# Blinky_v2.net
KiCad netlist of a schematic drawn in EAGLE
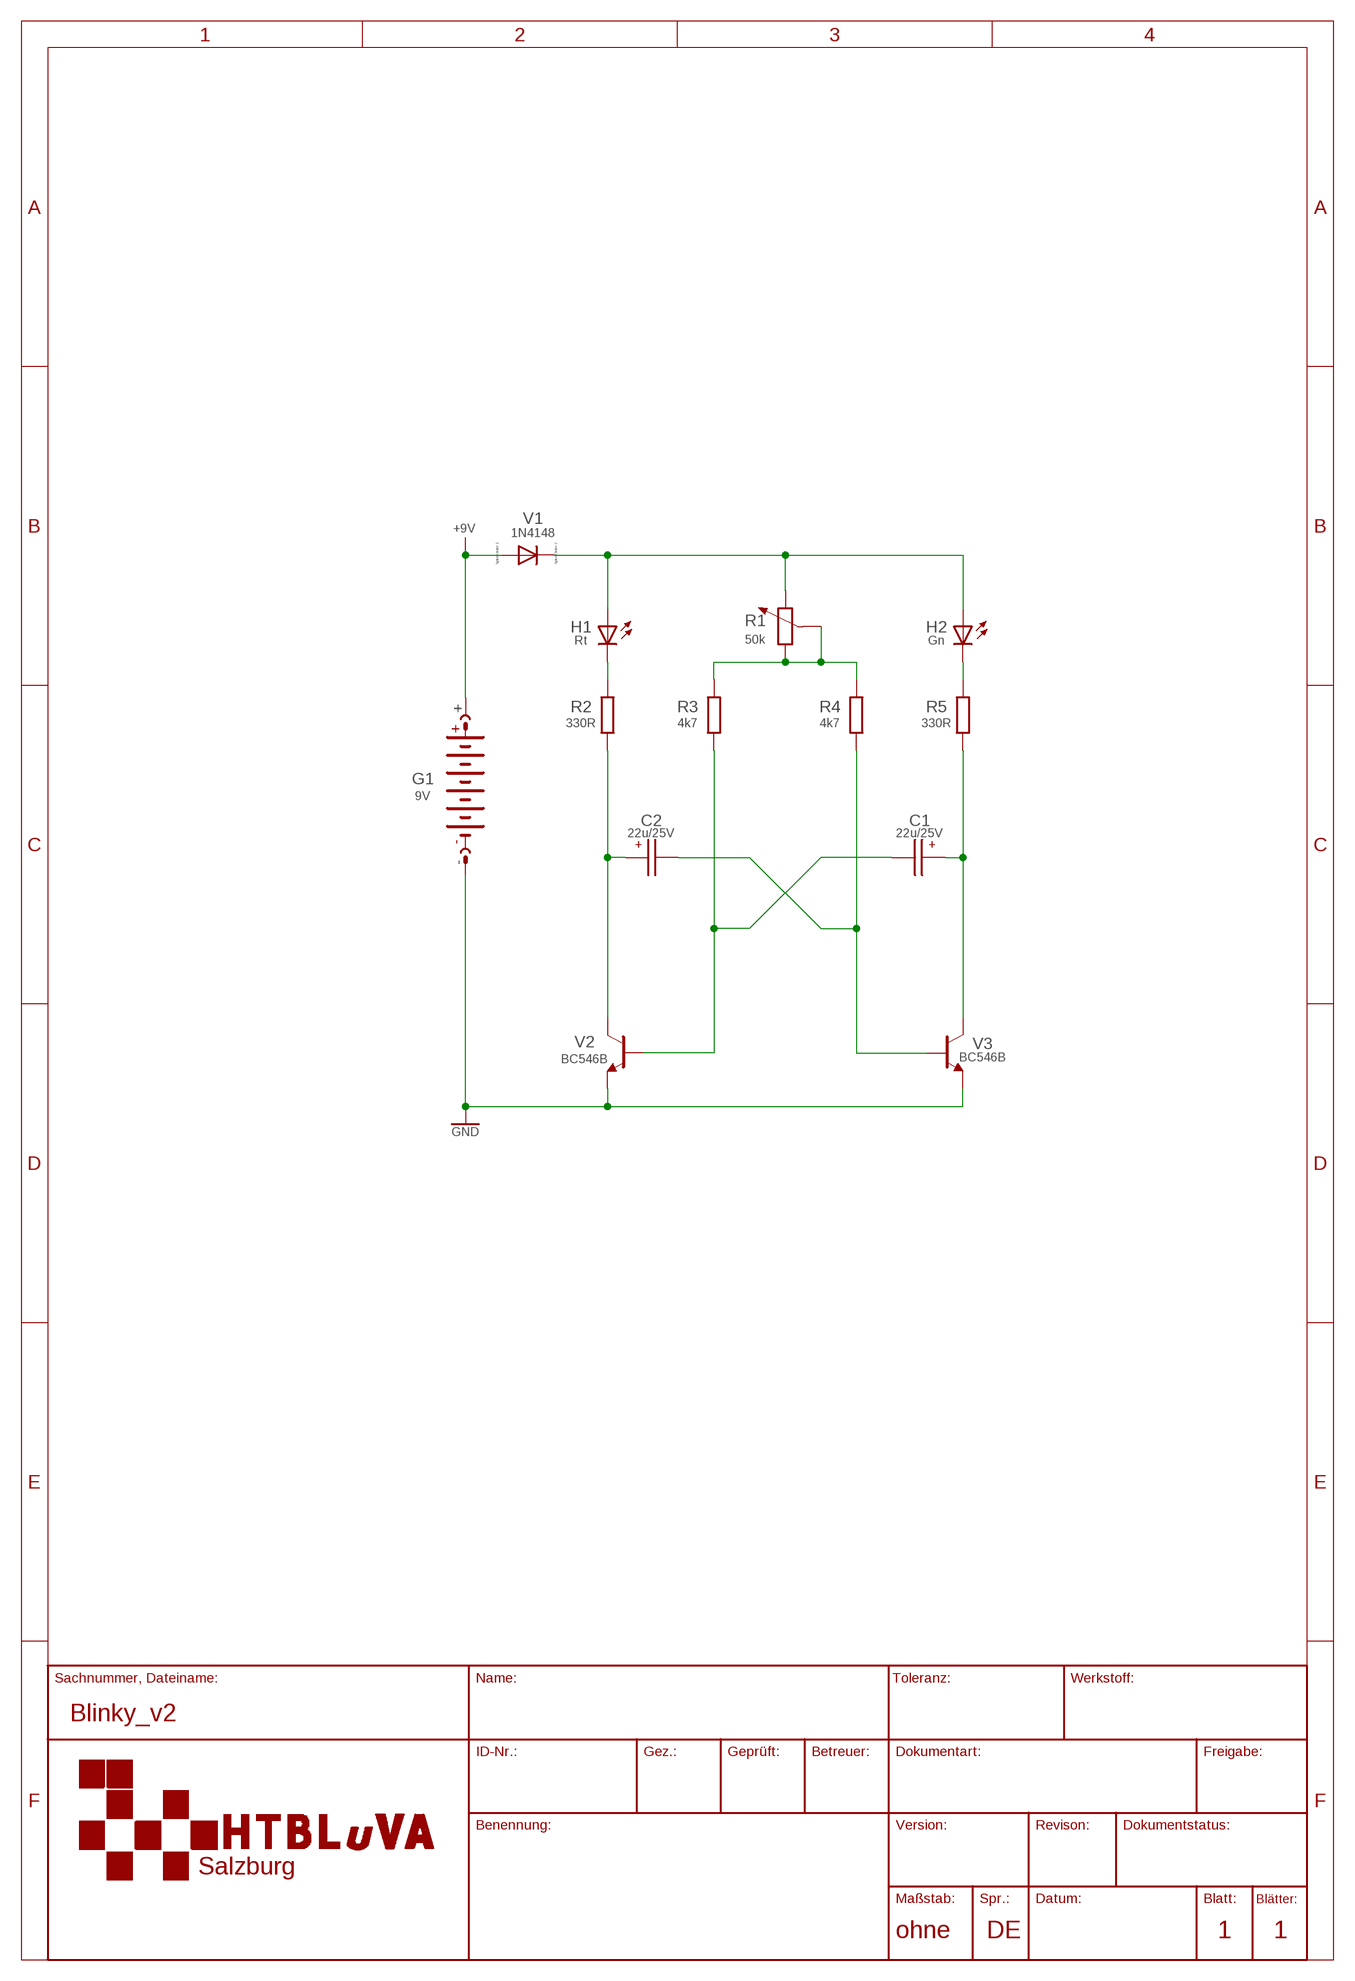
[diagram p0: schematic, sheet 1]

(export (version "E")
  (design (tool "Eeschema 10.0.6"))
  (components
    (comp (ref "C1")
      (value "22u/25V")
      (footprint "eagle-import:E2-5")
      (libsource (lib "eagle-import") (part "CPOL-V_E2-5"))
    )
    (comp (ref "C2")
      (value "22u/25V")
      (footprint "eagle-import:E2-5")
      (libsource (lib "eagle-import") (part "CPOL-V_E2-5"))
    )
    (comp (ref "G1")
      (value "9V")
      (footprint "eagle-import:AB9V")
      (libsource (lib "eagle-import") (part "AB9V9V"))
    )
    (comp (ref "H1")
      (value "Rt")
      (footprint "eagle-import:LED5MM")
      (libsource (lib "eagle-import") (part "LED_5MM"))
    )
    (comp (ref "H2")
      (value "Gn")
      (footprint "eagle-import:LED5MM")
      (libsource (lib "eagle-import") (part "LED_5MM"))
    )
    (comp (ref "R1")
      (value "50k")
      (footprint "eagle-import:PT-10")
      (libsource (lib "eagle-import") (part "R-POT_V_PT-10"))
    )
    (comp (ref "R2")
      (value "330R")
      (footprint "eagle-import:0207_10")
      (libsource (lib "eagle-import") (part "R-H_0207/10"))
    )
    (comp (ref "R3")
      (value "4k7")
      (footprint "eagle-import:0207_10")
      (libsource (lib "eagle-import") (part "R-H_0207/10"))
    )
    (comp (ref "R4")
      (value "4k7")
      (footprint "eagle-import:0207_10")
      (libsource (lib "eagle-import") (part "R-H_0207/10"))
    )
    (comp (ref "R5")
      (value "330R")
      (footprint "eagle-import:0207_10")
      (libsource (lib "eagle-import") (part "R-H_0207/10"))
    )
    (comp (ref "V1")
      (value "1N4148")
      (footprint "eagle-import:DO35-7")
      (libsource (lib "eagle-import") (part "1N4148_DO35-7"))
    )
    (comp (ref "V2")
      (value "BC546B")
      (footprint "eagle-import:TO92-EBC")
      (libsource (lib "eagle-import") (part "BC546B"))
    )
    (comp (ref "V3")
      (value "BC546B")
      (footprint "eagle-import:TO92-EBC")
      (libsource (lib "eagle-import") (part "BC546B"))
    )
  )
  (nets
    (net (code "1") (name "+9V") (class "Default")
      (node (ref "G1") (pin "+") (pinfunction "+_+") (pintype "passive"))
      (node (ref "V1") (pin "A") (pinfunction "A_A") (pintype "passive"))
    )
    (net (code "2") (name "GND") (class "Default")
      (node (ref "G1") (pin "-") (pinfunction "-_-") (pintype "passive"))
      (node (ref "V2") (pin "E") (pinfunction "E_E") (pintype "passive"))
      (node (ref "V3") (pin "E") (pinfunction "E_E") (pintype "passive"))
    )
    (net (code "3") (name "Net-(C1-Pad+)") (class "Default")
      (node (ref "C1") (pin "+") (pinfunction "+_+") (pintype "passive"))
      (node (ref "R5") (pin "1") (pinfunction "1_1") (pintype "passive"))
      (node (ref "V3") (pin "C") (pinfunction "C_C") (pintype "passive"))
    )
    (net (code "4") (name "Net-(C1-Pad-)") (class "Default")
      (node (ref "C1") (pin "-") (pinfunction "-_-") (pintype "passive"))
      (node (ref "R3") (pin "1") (pinfunction "1_1") (pintype "passive"))
      (node (ref "V2") (pin "B") (pinfunction "B_B") (pintype "passive"))
    )
    (net (code "5") (name "Net-(C2-Pad+)") (class "Default")
      (node (ref "C2") (pin "+") (pinfunction "+_+") (pintype "passive"))
      (node (ref "R2") (pin "1") (pinfunction "1_1") (pintype "passive"))
      (node (ref "V2") (pin "C") (pinfunction "C_C") (pintype "passive"))
    )
    (net (code "6") (name "Net-(C2-Pad-)") (class "Default")
      (node (ref "C2") (pin "-") (pinfunction "-_-") (pintype "passive"))
      (node (ref "R4") (pin "1") (pinfunction "1_1") (pintype "passive"))
      (node (ref "V3") (pin "B") (pinfunction "B_B") (pintype "passive"))
    )
    (net (code "7") (name "Net-(H1-C)") (class "Default")
      (node (ref "H1") (pin "K") (pinfunction "C_K") (pintype "passive"))
      (node (ref "R2") (pin "2") (pinfunction "2_2") (pintype "passive"))
    )
    (net (code "8") (name "Net-(H1-PadA)") (class "Default")
      (node (ref "H1") (pin "A") (pinfunction "A_A") (pintype "passive"))
      (node (ref "H2") (pin "A") (pinfunction "A_A") (pintype "passive"))
      (node (ref "R1") (pin "2") (pinfunction "2_2") (pintype "passive"))
      (node (ref "V1") (pin "C") (pinfunction "C_C") (pintype "passive"))
    )
    (net (code "9") (name "Net-(H2-C)") (class "Default")
      (node (ref "H2") (pin "K") (pinfunction "C_K") (pintype "passive"))
      (node (ref "R5") (pin "2") (pinfunction "2_2") (pintype "passive"))
    )
    (net (code "10") (name "Net-(R1-Pad1)") (class "Default")
      (node (ref "R1") (pin "1") (pinfunction "1_1") (pintype "passive"))
      (node (ref "R1") (pin "3") (pinfunction "3_3") (pintype "passive"))
      (node (ref "R3") (pin "2") (pinfunction "2_2") (pintype "passive"))
      (node (ref "R4") (pin "2") (pinfunction "2_2") (pintype "passive"))
    )
  )
)
